# Final.net
KiCad netlist of a schematic drawn in Altium Designer
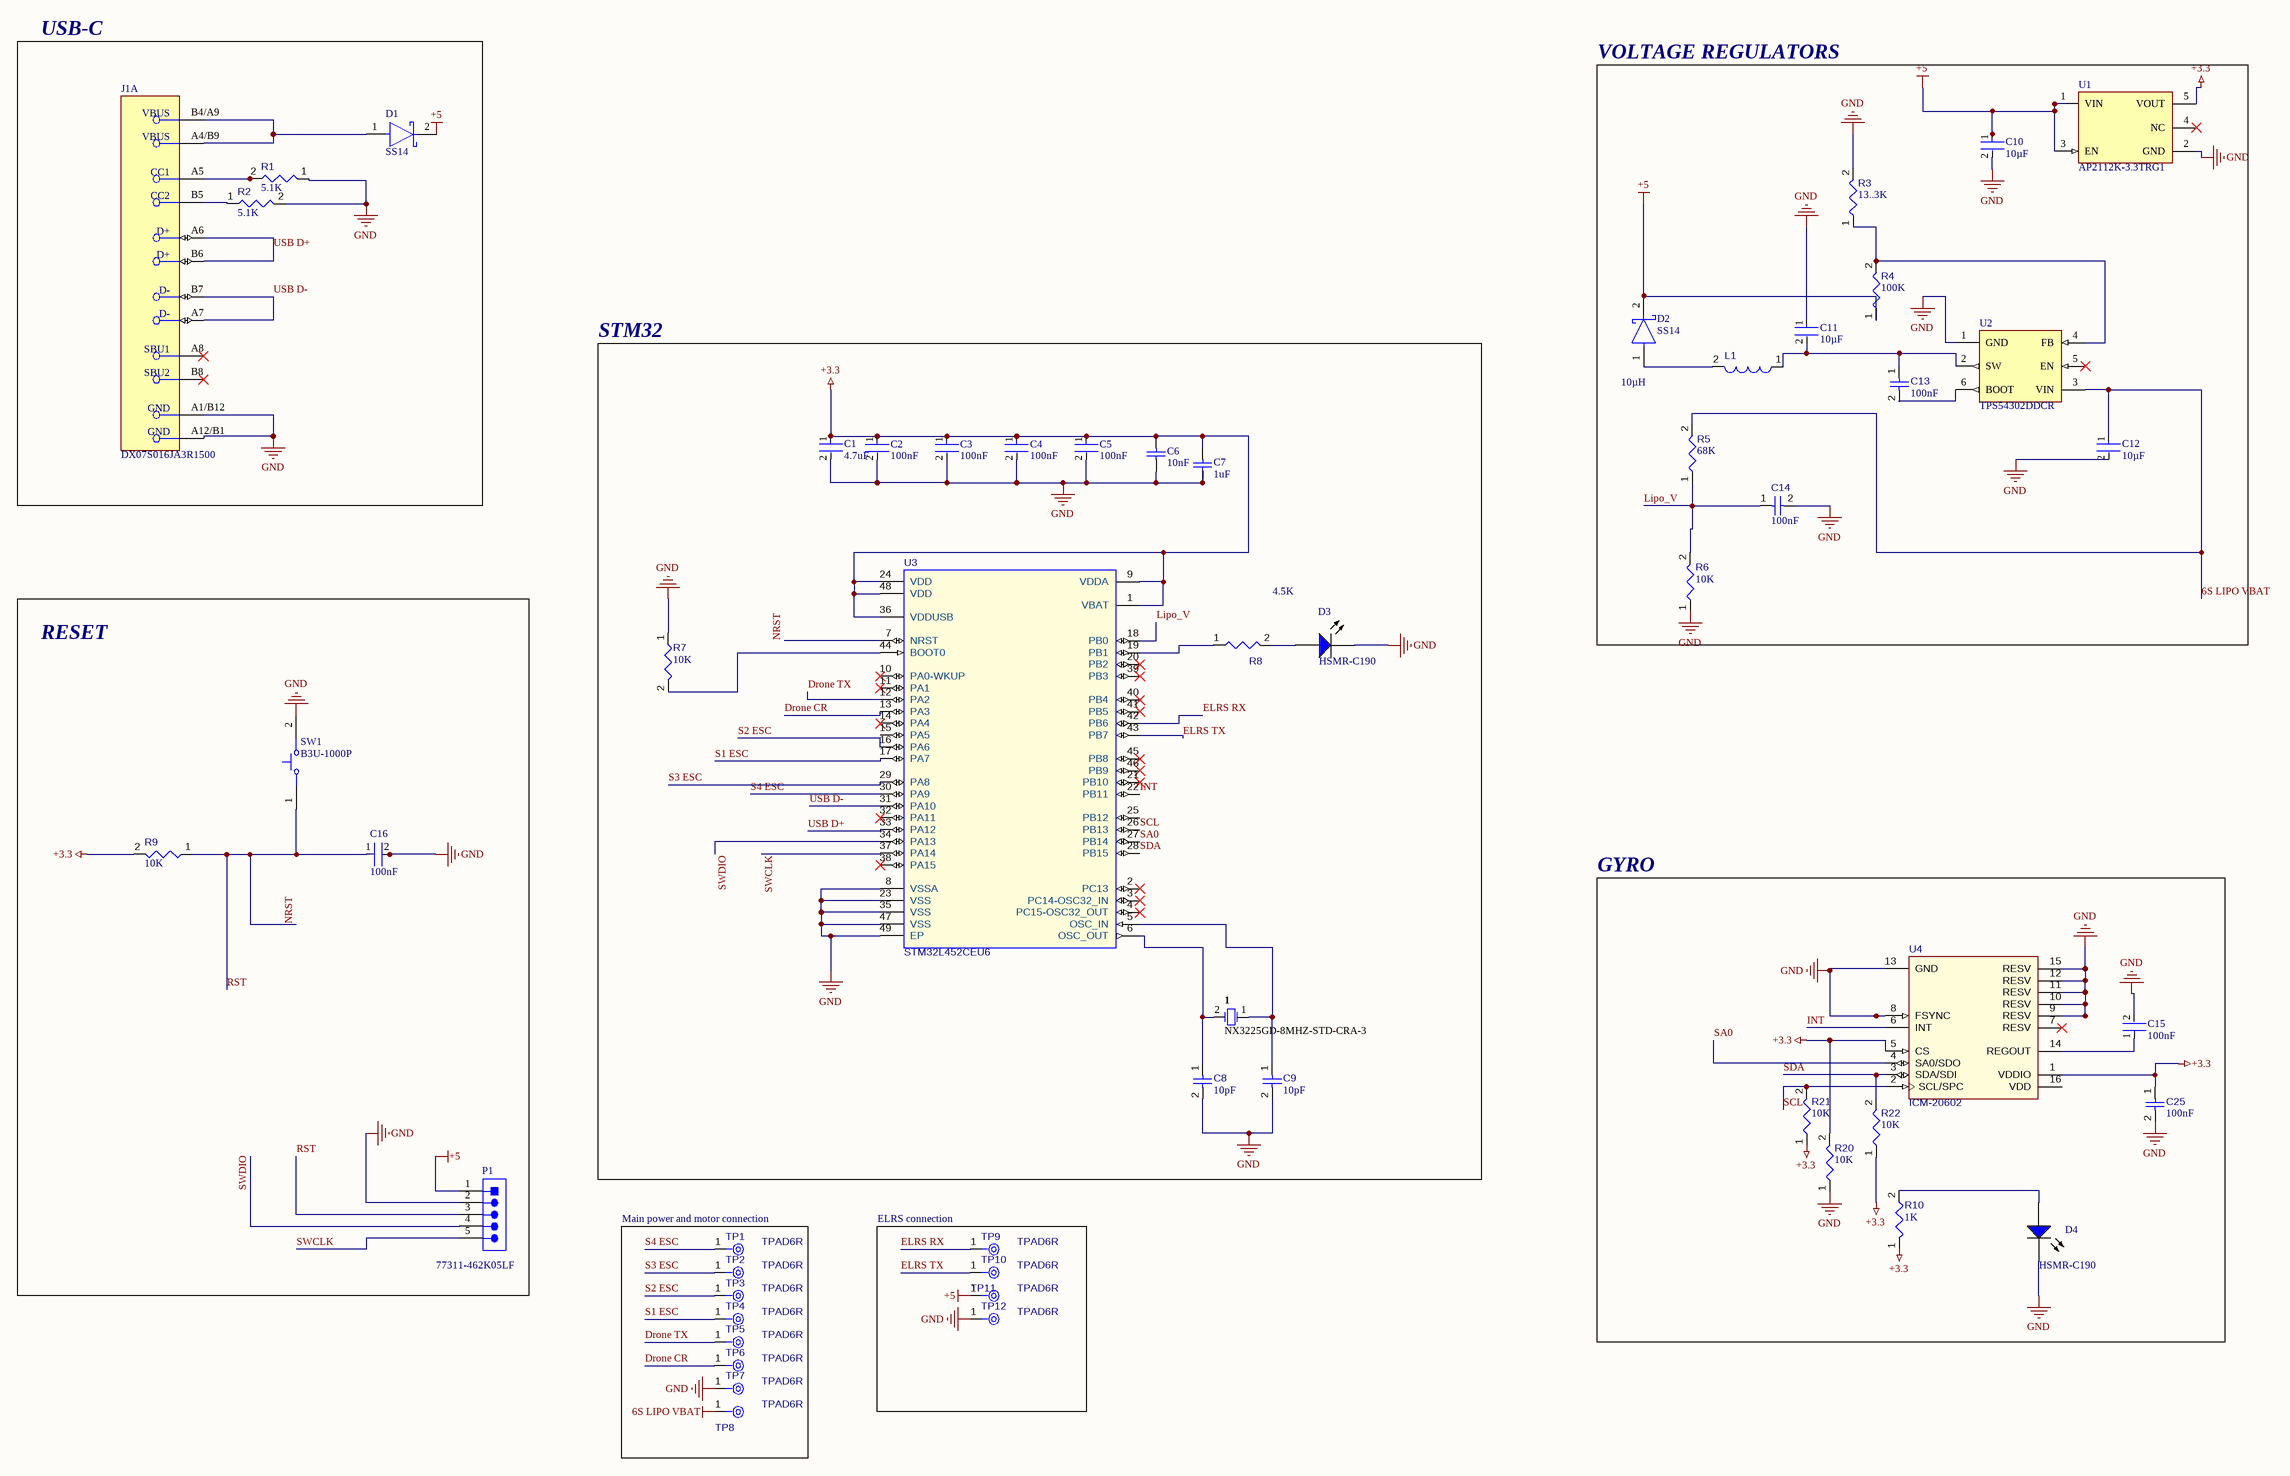
[diagram p0: Final.SchDoc]

(export (version "E")
  (design (tool "Eeschema 10.0.6"))
  (components
    (comp (ref "1")
      (value "NX3225GD-8MHZ-STD-CRA-3")
      (footprint "NDK-NX3225GD-8MHZ-STD-CRA-3_V")
      (description "Crystal Unit, 8 MHz, 8 pF, -40 to 150 degC, 2-Pin SMD, RoHS, Tape and Reel")
      (fields (field (name "MANUFACTURER") "NDK"))
      (libsource (lib "Altium Content Vault") (part "XTAL-1-2-2"))
    )
    (comp (ref "C1")
      (value "4.7uF")
      (footprint "FP-GRM188-0_15-MFG")
      (description "CAP CER 4.7UF 16V X5R 0603")
      (fields (field (name "TOLERANCE") "10%"))
      (libsource (lib "Altium Content Vault") (part "02cd4be3c70576c341d710602a673aa"))
    )
    (comp (ref "C2")
      (value "100nF")
      (footprint "FP-0402YC104KAT2A-MFG")
      (fields (field (name "TOLERANCE") "10%") (field (name "VOLTAGE") "16V"))
      (libsource (lib "Altium Content Vault") (part "02cd4be3c70576c341d710602a673aa"))
    )
    (comp (ref "C3")
      (value "100nF")
      (footprint "FP-0402YC104KAT2A-MFG")
      (fields (field (name "TOLERANCE") "10%") (field (name "VOLTAGE") "16V"))
      (libsource (lib "Altium Content Vault") (part "02cd4be3c70576c341d710602a673aa"))
    )
    (comp (ref "C4")
      (value "100nF")
      (footprint "FP-0402YC104KAT2A-MFG")
      (fields (field (name "TOLERANCE") "10%") (field (name "VOLTAGE") "16V"))
      (libsource (lib "Altium Content Vault") (part "02cd4be3c70576c341d710602a673aa"))
    )
    (comp (ref "C5")
      (value "100nF")
      (footprint "FP-0402YC104KAT2A-MFG")
      (fields (field (name "TOLERANCE") "10%") (field (name "VOLTAGE") "16V"))
      (libsource (lib "Altium Content Vault") (part "02cd4be3c70576c341d710602a673aa"))
    )
    (comp (ref "C6")
      (value "10nF")
      (footprint "CAPC1005X55X25LL05T10")
      (description "Chip Capacitor, 10 nF, 16 V, 10%, -55 to 125 degC, 0402 (1005 Metric), RoHS, Tape and Reel")
      (fields (field (name "MANUFACTURER") "Murata"))
      (libsource (lib "Altium Content Vault") (part "CAP-NP-2"))
    )
    (comp (ref "C7")
      (value "1uF")
      (footprint "CAPC1608X90X35NL10T15")
      (fields (field (name "MANUFACTURER") "Murata") (field (name "PART NUMBER") "GRM188R61C105KA12D"))
      (libsource (lib "Altium Content Vault") (part "CAP"))
    )
    (comp (ref "C8")
      (value "10pF")
      (footprint "CAPC1005X55X25ML05T05")
      (description "Chip Capacitor, 10 pF, +/- 5%, 50 V, 0402 (1005 Metric)")
      (fields (field (name "TOLERANCE") "5%") (field (name "Comment") "Capacitor 10 pF +/- 5% 50 V 0402"))
      (libsource (lib "Johnbright Onyeise") (part "CAP-NP-2"))
    )
    (comp (ref "C9")
      (value "10pF")
      (footprint "CAPC1005X55X25ML05T05")
      (description "Chip Capacitor, 10 pF, +/- 5%, 50 V, 0402 (1005 Metric)")
      (fields (field (name "TOLERANCE") "5%") (field (name "Comment") "Capacitor 10 pF +/- 5% 50 V 0402"))
      (libsource (lib "Johnbright Onyeise") (part "CAP-NP-2"))
    )
    (comp (ref "C10")
      (value "10µF")
      (footprint "FP-0805-L_2_0_0_15-W_1_25-MFG")
      (description "Multilayer Ceramic Capacitor 10 uF 16V X5R 10% SMD 0805 T/R")
      (fields (field (name "TOLERANCE") "10%"))
      (libsource (lib "Altium Content Vault") (part "02cd4be3c70576c341d710602a673aa"))
    )
    (comp (ref "C11")
      (value "10µF")
      (footprint "FP-0805-L_2_0_0_15-W_1_25-MFG")
      (description "Multilayer Ceramic Capacitor 10 uF 16V X5R 10% SMD 0805 T/R")
      (fields (field (name "TOLERANCE") "10%"))
      (libsource (lib "Altium Content Vault") (part "02cd4be3c70576c341d710602a673aa"))
    )
    (comp (ref "C12")
      (value "10µF")
      (footprint "FP-0805-L_2_0_0_15-W_1_25-MFG")
      (description "Multilayer Ceramic Capacitor 10 uF 16V X5R 10% SMD 0805 T/R")
      (fields (field (name "TOLERANCE") "10%"))
      (libsource (lib "Altium Content Vault") (part "02cd4be3c70576c341d710602a673aa"))
    )
    (comp (ref "C13")
      (value "100nF")
      (footprint "CAPC0402(1005)60_L")
      (description "Chip Capacitor, 100nF +/-20%, 50V, 0402, Thickness 0.6 mm")
      (fields (field (name "TOLERANCE") "10%") (field (name "Comment") "Capacitor 100nF +/-20% 50V 0402"))
      (libsource (lib "Johnbright Onyeise") (part "CAP-NP-2"))
    )
    (comp (ref "C14")
      (value "100nF")
      (footprint "CAPC0402(1005)60_L")
      (description "Chip Capacitor, 100nF +/-20%, 50V, 0402, Thickness 0.6 mm")
      (fields (field (name "TOLERANCE") "10%") (field (name "Comment") "Capacitor 100nF +/-20% 50V 0402"))
      (libsource (lib "Johnbright Onyeise") (part "CAP-NP-2"))
    )
    (comp (ref "C15")
      (value "100nF")
      (footprint "FP-0402YC104KAT2A-MFG")
      (fields (field (name "TOLERANCE") "10%") (field (name "VOLTAGE") "16V"))
      (libsource (lib "Altium Content Vault") (part "02cd4be3c70576c341d710602a673aa"))
    )
    (comp (ref "C16")
      (value "100nF")
      (footprint "FP-0402YC104KAT2A-MFG")
      (fields (field (name "TOLERANCE") "10%") (field (name "VOLTAGE") "16V"))
      (libsource (lib "Altium Content Vault") (part "02cd4be3c70576c341d710602a673aa"))
    )
    (comp (ref "C25")
      (value "100nF")
      (footprint "CAPC1005X56X25LL10T15")
      (description "Chip Capacitor, 0.1 uF, +/- 5%, 16 V, 0402 (1005 Metric)")
      (fields (field (name "TOLERANCE") "5%") (field (name "Comment") "Capacitor 0.1 uF +/- 5% 16 V 0402"))
      (libsource (lib "Johnbright Onyeise") (part "CAP-NP-2"))
    )
    (comp (ref "D1")
      (value "SS14")
      (footprint "FP-403AE-MFG")
      (description "DIODE SCHOTTKY 40V 1A SMA")
      (fields
        (field (name "MANUFACTURER") "ON Semiconductor")
        (field (name "OCTOPART") "https://octopart.com/ss14-on+semiconductor-29205033")
      )
      (libsource (lib "Altium Content Vault") (part "360ad2f4ac25a952324d13796385471"))
    )
    (comp (ref "D2")
      (value "SS14")
      (footprint "FP-403AE-MFG")
      (description "DIODE SCHOTTKY 40V 1A SMA")
      (fields
        (field (name "MANUFACTURER") "ON Semiconductor")
        (field (name "OCTOPART") "https://octopart.com/ss14-on+semiconductor-29205033")
      )
      (libsource (lib "Altium Content Vault") (part "360ad2f4ac25a952324d13796385471"))
    )
    (comp (ref "D3")
      (value "HSMR-C190")
      (footprint "AVAG-HSMX-C190_V")
      (description "LED Uni-Color Blue, 78 mW, 20 mA, -40 to 85 degC, 2-Pin SMD, RoHS, Tape and Reel")
      (fields (field (name "POWER") "78mW") (field (name "MANUFACTURER") "Avago"))
      (libsource (lib "Johnbright Onyeise") (part "LED-BLUE-AK-2"))
    )
    (comp (ref "D4")
      (value "HSMR-C190")
      (footprint "AVAG-HSMX-C190_V")
      (description "LED Uni-Color Blue, 78 mW, 20 mA, -40 to 85 degC, 2-Pin SMD, RoHS, Tape and Reel")
      (fields (field (name "POWER") "78mW") (field (name "MANUFACTURER") "Avago"))
      (libsource (lib "Johnbright Onyeise") (part "LED-BLUE-AK-2"))
    )
    (comp (ref "J1")
      (value "DX07S016JA3R1500")
      (footprint "FP-DX07S016JA3R1500-MFG")
      (description "CONN RCP USB2.0 TYP C 24P SMD RA")
      (libsource (lib "Altium Content Vault") (part "86c7019cab7ffbad937e454fd6d8a8a"))
    )
    (comp (ref "L1")
      (value "10µH")
      (footprint "INDC2520X100X60NL20T20")
      (description "Chip Inductor, 2.2 uH, +/- 20%, -55 to 125 degC, 1008 (2520 Metric), RoHS, Tape and Reel")
      (fields (field (name "TOLERANCE") "20%") (field (name "MANUFACTURER") "Murata"))
      (libsource (lib "Johnbright Onyeise") (part "IND-2"))
    )
    (comp (ref "P1")
      (value "77311-462K05LF")
      (footprint "FCI-77311-5_V")
      (fields (field (name "MANUFACTURER") "FCI Electronics"))
      (libsource (lib "Johnbright Onyeise") (part "CN-1P-M-R5"))
    )
    (comp (ref "R1")
      (value "5.1K")
      (footprint "RESC0402(1005)_L")
      (description "Chip Resistor, 2,37 kOhms, +/-1 %, 63 mW, -55 to 155 degC, 0402")
      (fields (field (name "POWER") "63mW") (field (name "TOLERANCE") "1%"))
      (libsource (lib "Johnbright Onyeise") (part "RES-2"))
    )
    (comp (ref "R2")
      (value "5.1K")
      (footprint "RESC0402(1005)_L")
      (description "Chip Resistor, 2,37 kOhms, +/-1 %, 63 mW, -55 to 155 degC, 0402")
      (fields (field (name "POWER") "63mW") (field (name "TOLERANCE") "1%"))
      (libsource (lib "") (part "RES-2_1"))
    )
    (comp (ref "R3")
      (value "13..3K")
      (footprint "RESC0402(1005)_L")
      (description "Chip Resistor, 2,37 kOhms, +/-1 %, 63 mW, -55 to 155 degC, 0402")
      (fields (field (name "POWER") "63mW") (field (name "TOLERANCE") "1%"))
      (libsource (lib "") (part "RES-2_1"))
    )
    (comp (ref "R4")
      (value "100K")
      (footprint "RESC0402(1005)_L")
      (description "100K 0.063W 1% 0402 (1005 Metric)  SMD")
      (fields (field (name "POWER") "63mW") (field (name "TOLERANCE") "1%"))
      (libsource (lib "Johnbright Onyeise") (part "100KR2F"))
    )
    (comp (ref "R5")
      (value "68K")
      (footprint "RESC0402(1005)_L")
      (description "Chip Resistor, 2,37 kOhms, +/-1 %, 63 mW, -55 to 155 degC, 0402")
      (fields (field (name "POWER") "63mW") (field (name "TOLERANCE") "1%"))
      (libsource (lib "") (part "RES-2_1"))
    )
    (comp (ref "R6")
      (value "10K")
      (footprint "RESC0402(1005)_L")
      (description "Chip Resistor, 2,37 kOhms, +/-1 %, 63 mW, -55 to 155 degC, 0402")
      (fields (field (name "POWER") "63mW") (field (name "TOLERANCE") "1%"))
      (libsource (lib "") (part "RES-2_1"))
    )
    (comp (ref "R7")
      (value "10K")
      (footprint "RESC0402(1005)_L")
      (description "Chip Resistor, 2,37 kOhms, +/-1 %, 63 mW, -55 to 155 degC, 0402")
      (fields (field (name "POWER") "63mW") (field (name "TOLERANCE") "1%"))
      (libsource (lib "") (part "RES-2_1"))
    )
    (comp (ref "R8")
      (value "4.5K")
      (footprint "RESC0402(1005)_L")
      (description "Chip Resistor, 2,37 kOhms, +/-1 %, 63 mW, -55 to 155 degC, 0402")
      (fields (field (name "POWER") "63mW") (field (name "TOLERANCE") "1%"))
      (libsource (lib "") (part "RES-2_1"))
    )
    (comp (ref "R9")
      (value "10K")
      (footprint "RESC0402(1005)_L")
      (description "Chip Resistor, 2,37 kOhms, +/-1 %, 63 mW, -55 to 155 degC, 0402")
      (fields (field (name "POWER") "63mW") (field (name "TOLERANCE") "1%"))
      (libsource (lib "") (part "RES-2_1"))
    )
    (comp (ref "R10")
      (value "1K")
      (footprint "RESC0402(1005)_L")
      (description "Chip Resistor, 2,37 kOhms, +/-1 %, 63 mW, -55 to 155 degC, 0402")
      (fields (field (name "POWER") "63mW") (field (name "TOLERANCE") "1%"))
      (libsource (lib "Johnbright Onyeise") (part "RES-2"))
    )
    (comp (ref "R20")
      (value "10K")
      (footprint "RESC0402(1005)_L")
      (description "Chip Resistor, 2,37 kOhms, +/-1 %, 63 mW, -55 to 155 degC, 0402")
      (fields (field (name "POWER") "63mW") (field (name "TOLERANCE") "1%"))
      (libsource (lib "") (part "RES-2_1"))
    )
    (comp (ref "R21")
      (value "10K")
      (footprint "RESC0402(1005)_L")
      (description "Chip Resistor, 2,37 kOhms, +/-1 %, 63 mW, -55 to 155 degC, 0402")
      (fields (field (name "POWER") "63mW") (field (name "TOLERANCE") "1%"))
      (libsource (lib "") (part "RES-2_1"))
    )
    (comp (ref "R22")
      (value "10K")
      (footprint "RESC0402(1005)_L")
      (description "Chip Resistor, 2,37 kOhms, +/-1 %, 63 mW, -55 to 155 degC, 0402")
      (fields (field (name "POWER") "63mW") (field (name "TOLERANCE") "1%"))
      (libsource (lib "") (part "RES-2_1"))
    )
    (comp (ref "SW1")
      (value "B3U-1000P")
      (footprint "OMRON-B3U-1000_V")
      (description "Tactile Switch, SPST-NO, 0.05 A, 12 V, -25 to 70 degC, 2-Pin SMD, RoHS, Tape and Reel")
      (fields (field (name "MANUFACTURER") "Omron Electronic Components"))
      (libsource (lib "Johnbright Onyeise") (part "SW-SPST-NO-2"))
    )
    (comp (ref "TP1")
      (value "TPAD6R")
      (footprint "TP06R")
      (description "0.6mm round")
      (libsource (lib "Johnbright Onyeise") (part "CMP-001-0001-4"))
    )
    (comp (ref "TP2")
      (value "TPAD6R")
      (footprint "TP06R")
      (description "0.6mm round")
      (libsource (lib "Johnbright Onyeise") (part "CMP-001-0001-4"))
    )
    (comp (ref "TP3")
      (value "TPAD6R")
      (footprint "TP06R")
      (description "0.6mm round")
      (libsource (lib "Johnbright Onyeise") (part "CMP-001-0001-4"))
    )
    (comp (ref "TP4")
      (value "TPAD6R")
      (footprint "TP06R")
      (description "0.6mm round")
      (libsource (lib "Johnbright Onyeise") (part "CMP-001-0001-4"))
    )
    (comp (ref "TP5")
      (value "TPAD6R")
      (footprint "TP06R")
      (description "0.6mm round")
      (libsource (lib "Johnbright Onyeise") (part "CMP-001-0001-4"))
    )
    (comp (ref "TP6")
      (value "TPAD6R")
      (footprint "TP06R")
      (description "0.6mm round")
      (libsource (lib "Johnbright Onyeise") (part "CMP-001-0001-4"))
    )
    (comp (ref "TP7")
      (value "TPAD6R")
      (footprint "TP06R")
      (description "0.6mm round")
      (libsource (lib "Johnbright Onyeise") (part "CMP-001-0001-4"))
    )
    (comp (ref "TP8")
      (value "TPAD6R")
      (footprint "TP06R")
      (description "0.6mm round")
      (libsource (lib "Johnbright Onyeise") (part "CMP-001-0001-4"))
    )
    (comp (ref "TP9")
      (value "TPAD6R")
      (footprint "TP06R")
      (description "0.6mm round")
      (libsource (lib "Johnbright Onyeise") (part "CMP-001-0001-4"))
    )
    (comp (ref "TP10")
      (value "TPAD6R")
      (footprint "TP06R")
      (description "0.6mm round")
      (libsource (lib "Johnbright Onyeise") (part "CMP-001-0001-4"))
    )
    (comp (ref "TP11")
      (value "TPAD6R")
      (footprint "TP06R")
      (description "0.6mm round")
      (libsource (lib "Johnbright Onyeise") (part "CMP-001-0001-4"))
    )
    (comp (ref "TP12")
      (value "TPAD6R")
      (footprint "TP06R")
      (description "0.6mm round")
      (libsource (lib "Johnbright Onyeise") (part "CMP-001-0001-4"))
    )
    (comp (ref "U1")
      (value "AP2112K-3.3TRG1")
      (footprint "FP-SOT25-IPC_A")
      (description "IC REG LINEAR 3.3V 600MA SOT25")
      (libsource (lib "Altium Content Vault") (part "c8ab751aee5229183125ab046a11caa"))
    )
    (comp (ref "U2")
      (value "TPS54302DDCR")
      (footprint "FP-DDC0006A-MFG")
      (description "IC REG BUCK ADJ 3A TSOT23-6")
      (fields
        (field (name "MANUFACTURER") "Texas Instruments")
        (field (name "OCTOPART") "https://octopart.com/tps54302ddcr-texas+instruments-74209025")
      )
      (libsource (lib "Altium Content Vault") (part "e6e62595b56d4ede9a2c24ebe42f01f"))
    )
    (comp (ref "U3")
      (value "STM32L452CEU6")
      (footprint "STM-UFQFPN48_N")
      (description "ARM® Cortex®-M4 STM32L4 Microcontroller IC 32-Bit 80MHz 512KB (512K x 8) FLASH 48-UFQFPN (7x7)")
      (libsource (lib "Johnbright Onyeise") (part "CMP-00133-5"))
    )
    (comp (ref "U4")
      (value "ICM-20602")
      (footprint "INSE-I62-16")
      (libsource (lib "Johnbright Onyeise") (part "CMP-00120-6"))
    )
  )
  (nets
    (net (code "1") (name "+3.3") (class "Default")
      (node (ref "C1") (pin "1") (pinfunction "1_1") (pintype "passive"))
      (node (ref "C2") (pin "1") (pinfunction "1_1") (pintype "passive"))
      (node (ref "C25") (pin "1") (pinfunction "1_1") (pintype "passive"))
      (node (ref "C3") (pin "1") (pinfunction "1_1") (pintype "passive"))
      (node (ref "C4") (pin "1") (pinfunction "1_1") (pintype "passive"))
      (node (ref "C5") (pin "1") (pinfunction "1_1") (pintype "passive"))
      (node (ref "C6") (pin "1") (pinfunction "1_1") (pintype "passive"))
      (node (ref "C7") (pin "2") (pinfunction "2_2") (pintype "passive"))
      (node (ref "R10") (pin "1") (pinfunction "1_1") (pintype "passive"))
      (node (ref "R20") (pin "2") (pinfunction "2_2") (pintype "passive"))
      (node (ref "R21") (pin "1") (pinfunction "1_1") (pintype "passive"))
      (node (ref "R22") (pin "1") (pinfunction "1_1") (pintype "passive"))
      (node (ref "R9") (pin "2") (pinfunction "2_2") (pintype "passive"))
      (node (ref "U1") (pin "5") (pinfunction "VOUT_5") (pintype "power_in"))
      (node (ref "U3") (pin "1") (pinfunction "VBAT_1") (pintype "power_in"))
      (node (ref "U3") (pin "24") (pinfunction "VDD_24") (pintype "power_in"))
      (node (ref "U3") (pin "36") (pinfunction "VDDUSB_36") (pintype "power_in"))
      (node (ref "U3") (pin "48") (pinfunction "VDD_48") (pintype "power_in"))
      (node (ref "U3") (pin "9") (pinfunction "VDDA_9") (pintype "power_in"))
      (node (ref "U4") (pin "1") (pinfunction "VDDIO_1") (pintype "power_in"))
      (node (ref "U4") (pin "5") (pinfunction "CS_5") (pintype "input"))
    )
    (net (code "2") (name "+5") (class "Default")
      (node (ref "C10") (pin "1") (pinfunction "1_1") (pintype "passive"))
      (node (ref "D1") (pin "2") (pinfunction "C_2") (pintype "passive"))
      (node (ref "D2") (pin "2") (pinfunction "C_2") (pintype "passive"))
      (node (ref "P1") (pin "1") (pinfunction "DTR_1") (pintype "passive"))
      (node (ref "R4") (pin "1") (pinfunction "1_1") (pintype "passive"))
      (node (ref "TP11") (pin "1") (pinfunction "TP_1") (pintype "passive"))
      (node (ref "U1") (pin "1") (pinfunction "VIN_1") (pintype "power_in"))
      (node (ref "U1") (pin "3") (pinfunction "EN_3") (pintype "input"))
    )
    (net (code "3") (name "/Drone CR") (class "Default")
      (node (ref "TP6") (pin "1") (pinfunction "TP_1") (pintype "passive"))
      (node (ref "U3") (pin "13") (pinfunction "PA3_13") (pintype "bidirectional"))
    )
    (net (code "4") (name "/Drone TX") (class "Default")
      (node (ref "TP5") (pin "1") (pinfunction "TP_1") (pintype "passive"))
      (node (ref "U3") (pin "12") (pinfunction "PA2_12") (pintype "bidirectional"))
    )
    (net (code "5") (name "/ELRS RX") (class "Default")
      (node (ref "TP9") (pin "1") (pinfunction "TP_1") (pintype "passive"))
      (node (ref "U3") (pin "42") (pinfunction "PB6_42") (pintype "bidirectional"))
    )
    (net (code "6") (name "/ELRS TX") (class "Default")
      (node (ref "TP10") (pin "1") (pinfunction "TP_1") (pintype "passive"))
      (node (ref "U3") (pin "43") (pinfunction "PB7_43") (pintype "bidirectional"))
    )
    (net (code "7") (name "/INT") (class "Default")
      (node (ref "U3") (pin "22") (pinfunction "PB11_22") (pintype "bidirectional"))
      (node (ref "U4") (pin "6") (pinfunction "INT_6") (pintype "open_collector"))
    )
    (net (code "8") (name "/Lipo_V") (class "Default")
      (node (ref "C14") (pin "1") (pinfunction "1_1") (pintype "passive"))
      (node (ref "R5") (pin "1") (pinfunction "1_1") (pintype "passive"))
      (node (ref "R6") (pin "2") (pinfunction "2_2") (pintype "passive"))
      (node (ref "U3") (pin "18") (pinfunction "PB0_18") (pintype "bidirectional"))
    )
    (net (code "9") (name "/NRST") (class "Default")
      (node (ref "C16") (pin "1") (pinfunction "1_1") (pintype "passive"))
      (node (ref "P1") (pin "3") (pinfunction "TXO_3") (pintype "passive"))
      (node (ref "R9") (pin "1") (pinfunction "1_1") (pintype "passive"))
      (node (ref "SW1") (pin "1") (pinfunction "1_1") (pintype "passive"))
      (node (ref "U3") (pin "7") (pinfunction "NRST_7") (pintype "bidirectional"))
    )
    (net (code "10") (name "/S1 ESC") (class "Default")
      (node (ref "TP4") (pin "1") (pinfunction "TP_1") (pintype "passive"))
      (node (ref "U3") (pin "17") (pinfunction "PA7_17") (pintype "bidirectional"))
    )
    (net (code "11") (name "/S2 ESC") (class "Default")
      (node (ref "TP3") (pin "1") (pinfunction "TP_1") (pintype "passive"))
      (node (ref "U3") (pin "16") (pinfunction "PA6_16") (pintype "bidirectional"))
    )
    (net (code "12") (name "/S3 ESC") (class "Default")
      (node (ref "TP2") (pin "1") (pinfunction "TP_1") (pintype "passive"))
      (node (ref "U3") (pin "29") (pinfunction "PA8_29") (pintype "bidirectional"))
    )
    (net (code "13") (name "/S4 ESC") (class "Default")
      (node (ref "TP1") (pin "1") (pinfunction "TP_1") (pintype "passive"))
      (node (ref "U3") (pin "30") (pinfunction "PA9_30") (pintype "bidirectional"))
    )
    (net (code "14") (name "/SA0") (class "Default")
      (node (ref "U3") (pin "27") (pinfunction "PB14_27") (pintype "bidirectional"))
      (node (ref "U4") (pin "4") (pinfunction "SA0/SDO_4") (pintype "bidirectional"))
    )
    (net (code "15") (name "/SCL") (class "Default")
      (node (ref "R21") (pin "2") (pinfunction "2_2") (pintype "passive"))
      (node (ref "U3") (pin "26") (pinfunction "PB13_26") (pintype "bidirectional"))
      (node (ref "U4") (pin "2") (pinfunction "SCL/SPC_2") (pintype "input"))
    )
    (net (code "16") (name "/SDA") (class "Default")
      (node (ref "R22") (pin "2") (pinfunction "2_2") (pintype "passive"))
      (node (ref "U3") (pin "28") (pinfunction "PB15_28") (pintype "bidirectional"))
      (node (ref "U4") (pin "3") (pinfunction "SDA/SDI_3") (pintype "bidirectional"))
    )
    (net (code "17") (name "/SWCLK") (class "Default")
      (node (ref "P1") (pin "5") (pinfunction "CTS_5") (pintype "passive"))
      (node (ref "U3") (pin "37") (pinfunction "PA14_37") (pintype "bidirectional"))
    )
    (net (code "18") (name "/SWDIO") (class "Default")
      (node (ref "P1") (pin "4") (pinfunction "VCC_4") (pintype "passive"))
      (node (ref "U3") (pin "34") (pinfunction "PA13_34") (pintype "bidirectional"))
    )
    (net (code "19") (name "/USB D+") (class "Default")
      (node (ref "J1") (pin "A6") (pinfunction "D+_A6") (pintype "bidirectional"))
      (node (ref "J1") (pin "B6") (pinfunction "D+_B6") (pintype "bidirectional"))
      (node (ref "U3") (pin "33") (pinfunction "PA12_33") (pintype "bidirectional"))
    )
    (net (code "20") (name "/USB D-") (class "Default")
      (node (ref "J1") (pin "A7") (pinfunction "D-_A7") (pintype "bidirectional"))
      (node (ref "J1") (pin "B7") (pinfunction "D-_B7") (pintype "bidirectional"))
      (node (ref "U3") (pin "31") (pinfunction "PA10_31") (pintype "bidirectional"))
    )
    (net (code "21") (name "6S LIPO VBAT") (class "Default")
      (node (ref "C12") (pin "1") (pinfunction "1_1") (pintype "passive"))
      (node (ref "R5") (pin "2") (pinfunction "2_2") (pintype "passive"))
      (node (ref "TP8") (pin "1") (pinfunction "TP_1") (pintype "passive"))
      (node (ref "U2") (pin "3") (pinfunction "VIN_3") (pintype "power_in"))
    )
    (net (code "22") (name "GND") (class "Default")
      (node (ref "C1") (pin "2") (pinfunction "2_2") (pintype "passive"))
      (node (ref "C10") (pin "2") (pinfunction "2_2") (pintype "passive"))
      (node (ref "C11") (pin "1") (pinfunction "1_1") (pintype "passive"))
      (node (ref "C12") (pin "2") (pinfunction "2_2") (pintype "passive"))
      (node (ref "C14") (pin "2") (pinfunction "2_2") (pintype "passive"))
      (node (ref "C15") (pin "2") (pinfunction "2_2") (pintype "passive"))
      (node (ref "C16") (pin "2") (pinfunction "2_2") (pintype "passive"))
      (node (ref "C2") (pin "2") (pinfunction "2_2") (pintype "passive"))
      (node (ref "C25") (pin "2") (pinfunction "2_2") (pintype "passive"))
      (node (ref "C3") (pin "2") (pinfunction "2_2") (pintype "passive"))
      (node (ref "C4") (pin "2") (pinfunction "2_2") (pintype "passive"))
      (node (ref "C5") (pin "2") (pinfunction "2_2") (pintype "passive"))
      (node (ref "C6") (pin "2") (pinfunction "2_2") (pintype "passive"))
      (node (ref "C7") (pin "1") (pinfunction "1_1") (pintype "passive"))
      (node (ref "C8") (pin "2") (pinfunction "2_2") (pintype "passive"))
      (node (ref "C9") (pin "2") (pinfunction "2_2") (pintype "passive"))
      (node (ref "D3") (pin "2") (pinfunction "K_2") (pintype "passive"))
      (node (ref "D4") (pin "2") (pinfunction "K_2") (pintype "passive"))
      (node (ref "J1") (pin "A1/B12") (pinfunction "GND_A1/B12") (pintype "power_in"))
      (node (ref "J1") (pin "A12/B1") (pinfunction "GND_A12/B1") (pintype "power_in"))
      (node (ref "P1") (pin "2") (pinfunction "RXI_2") (pintype "passive"))
      (node (ref "R1") (pin "1") (pinfunction "1_1") (pintype "passive"))
      (node (ref "R2") (pin "2") (pinfunction "2_2") (pintype "passive"))
      (node (ref "R20") (pin "1") (pinfunction "1_1") (pintype "passive"))
      (node (ref "R3") (pin "2") (pinfunction "2_2") (pintype "passive"))
      (node (ref "R6") (pin "1") (pinfunction "1_1") (pintype "passive"))
      (node (ref "R7") (pin "1") (pinfunction "1_1") (pintype "passive"))
      (node (ref "SW1") (pin "2") (pinfunction "2_2") (pintype "passive"))
      (node (ref "TP12") (pin "1") (pinfunction "TP_1") (pintype "passive"))
      (node (ref "TP7") (pin "1") (pinfunction "TP_1") (pintype "passive"))
      (node (ref "U1") (pin "2") (pinfunction "GND_2") (pintype "power_in"))
      (node (ref "U2") (pin "1") (pinfunction "GND_1") (pintype "power_in"))
      (node (ref "U3") (pin "23") (pinfunction "VSS_23") (pintype "power_in"))
      (node (ref "U3") (pin "35") (pinfunction "VSS_35") (pintype "power_in"))
      (node (ref "U3") (pin "47") (pinfunction "VSS_47") (pintype "power_in"))
      (node (ref "U3") (pin "49") (pinfunction "EP_49") (pintype "passive"))
      (node (ref "U3") (pin "8") (pinfunction "VSSA_8") (pintype "power_in"))
      (node (ref "U4") (pin "10") (pinfunction "RESV_10") (pintype "passive"))
      (node (ref "U4") (pin "11") (pinfunction "RESV_11") (pintype "passive"))
      (node (ref "U4") (pin "12") (pinfunction "RESV_12") (pintype "passive"))
      (node (ref "U4") (pin "13") (pinfunction "GND_13") (pintype "power_in"))
      (node (ref "U4") (pin "15") (pinfunction "RESV_15") (pintype "passive"))
      (node (ref "U4") (pin "8") (pinfunction "FSYNC_8") (pintype "input"))
      (node (ref "U4") (pin "9") (pinfunction "RESV_9") (pintype "passive"))
    )
    (net (code "23") (name "Net-(D1-A)") (class "Default")
      (node (ref "D1") (pin "1") (pinfunction "A_1") (pintype "passive"))
      (node (ref "J1") (pin "A4/B9") (pinfunction "VBUS_A4/B9") (pintype "power_in"))
      (node (ref "J1") (pin "B4/A9") (pinfunction "VBUS_B4/A9") (pintype "power_in"))
    )
    (net (code "24") (name "Net-(D2-A)") (class "Default")
      (node (ref "D2") (pin "1") (pinfunction "A_1") (pintype "passive"))
      (node (ref "L1") (pin "2") (pinfunction "2_2") (pintype "passive"))
    )
    (net (code "25") (name "Net-(D3-A)") (class "Default")
      (node (ref "D3") (pin "1") (pinfunction "A_1") (pintype "passive"))
      (node (ref "R8") (pin "2") (pinfunction "2_2") (pintype "passive"))
    )
    (net (code "26") (name "Net-(D4-A)") (class "Default")
      (node (ref "D4") (pin "1") (pinfunction "A_1") (pintype "passive"))
      (node (ref "R10") (pin "2") (pinfunction "2_2") (pintype "passive"))
    )
    (net (code "27") (name "Net-(J1A-CC1)") (class "Default")
      (node (ref "J1") (pin "A5") (pinfunction "CC1_A5") (pintype "passive"))
      (node (ref "R1") (pin "2") (pinfunction "2_2") (pintype "passive"))
    )
    (net (code "28") (name "Net-(J1A-CC2)") (class "Default")
      (node (ref "J1") (pin "B5") (pinfunction "CC2_B5") (pintype "passive"))
      (node (ref "R2") (pin "1") (pinfunction "1_1") (pintype "passive"))
    )
    (net (code "29") (name "Net-(U2-BOOT)") (class "Default")
      (node (ref "C13") (pin "2") (pinfunction "2_2") (pintype "passive"))
      (node (ref "U2") (pin "6") (pinfunction "BOOT_6") (pintype "output"))
    )
    (net (code "30") (name "Net-(U2-FB)") (class "Default")
      (node (ref "R3") (pin "1") (pinfunction "1_1") (pintype "passive"))
      (node (ref "R4") (pin "2") (pinfunction "2_2") (pintype "passive"))
      (node (ref "U2") (pin "4") (pinfunction "FB_4") (pintype "input"))
    )
    (net (code "31") (name "Net-(U2-SW)") (class "Default")
      (node (ref "C11") (pin "2") (pinfunction "2_2") (pintype "passive"))
      (node (ref "C13") (pin "1") (pinfunction "1_1") (pintype "passive"))
      (node (ref "L1") (pin "1") (pinfunction "1_1") (pintype "passive"))
      (node (ref "U2") (pin "2") (pinfunction "SW_2") (pintype "output"))
    )
    (net (code "32") (name "Net-(U3-BOOT0)") (class "Default")
      (node (ref "R7") (pin "2") (pinfunction "2_2") (pintype "passive"))
      (node (ref "U3") (pin "44") (pinfunction "BOOT0_44") (pintype "input"))
    )
    (net (code "33") (name "Net-(U3-OSC_IN)") (class "Default")
      (node (ref "1") (pin "1") (pinfunction "1_1") (pintype "passive"))
      (node (ref "C9") (pin "1") (pinfunction "1_1") (pintype "passive"))
      (node (ref "U3") (pin "5") (pinfunction "OSC_IN_5") (pintype "input"))
    )
    (net (code "34") (name "Net-(U3-OSC_OUT)") (class "Default")
      (node (ref "1") (pin "2") (pinfunction "2_2") (pintype "passive"))
      (node (ref "C8") (pin "1") (pinfunction "1_1") (pintype "passive"))
      (node (ref "U3") (pin "6") (pinfunction "OSC_OUT_6") (pintype "output"))
    )
    (net (code "35") (name "Net-(U3-PB1)") (class "Default")
      (node (ref "R8") (pin "1") (pinfunction "1_1") (pintype "passive"))
      (node (ref "U3") (pin "19") (pinfunction "PB1_19") (pintype "bidirectional"))
    )
    (net (code "36") (name "Net-(U4-REGOUT)") (class "Default")
      (node (ref "C15") (pin "1") (pinfunction "1_1") (pintype "passive"))
      (node (ref "U4") (pin "14") (pinfunction "REGOUT_14") (pintype "passive"))
    )
    (net (code "37") (name "unconnected-(J1A-SBU1-PadA8)") (class "Default")
      (node (ref "J1") (pin "A8") (pinfunction "SBU1_A8") (pintype "passive+no_connect"))
    )
    (net (code "38") (name "unconnected-(J1A-SBU2-PadB8)") (class "Default")
      (node (ref "J1") (pin "B8") (pinfunction "SBU2_B8") (pintype "passive+no_connect"))
    )
    (net (code "39") (name "unconnected-(U1-NC-Pad4)") (class "Default")
      (node (ref "U1") (pin "4") (pinfunction "NC_4") (pintype "passive+no_connect"))
    )
    (net (code "40") (name "unconnected-(U2-EN-Pad5)") (class "Default")
      (node (ref "U2") (pin "5") (pinfunction "EN_5") (pintype "input+no_connect"))
    )
    (net (code "41") (name "unconnected-(U3-PA0-WKUP-Pad10)") (class "Default")
      (node (ref "U3") (pin "10") (pinfunction "PA0-WKUP_10") (pintype "bidirectional+no_connect"))
    )
    (net (code "42") (name "unconnected-(U3-PA1-Pad11)") (class "Default")
      (node (ref "U3") (pin "11") (pinfunction "PA1_11") (pintype "bidirectional+no_connect"))
    )
    (net (code "43") (name "unconnected-(U3-PA4-Pad14)") (class "Default")
      (node (ref "U3") (pin "14") (pinfunction "PA4_14") (pintype "bidirectional+no_connect"))
    )
    (net (code "44") (name "unconnected-(U3-PA5-Pad15)") (class "Default")
      (node (ref "U3") (pin "15") (pinfunction "PA5_15") (pintype "bidirectional"))
    )
    (net (code "45") (name "unconnected-(U3-PA11-Pad32)") (class "Default")
      (node (ref "U3") (pin "32") (pinfunction "PA11_32") (pintype "bidirectional+no_connect"))
    )
    (net (code "46") (name "unconnected-(U3-PA15-Pad38)") (class "Default")
      (node (ref "U3") (pin "38") (pinfunction "PA15_38") (pintype "bidirectional+no_connect"))
    )
    (net (code "47") (name "unconnected-(U3-PB2-Pad20)") (class "Default")
      (node (ref "U3") (pin "20") (pinfunction "PB2_20") (pintype "bidirectional+no_connect"))
    )
    (net (code "48") (name "unconnected-(U3-PB3-Pad39)") (class "Default")
      (node (ref "U3") (pin "39") (pinfunction "PB3_39") (pintype "bidirectional+no_connect"))
    )
    (net (code "49") (name "unconnected-(U3-PB4-Pad40)") (class "Default")
      (node (ref "U3") (pin "40") (pinfunction "PB4_40") (pintype "bidirectional+no_connect"))
    )
    (net (code "50") (name "unconnected-(U3-PB5-Pad41)") (class "Default")
      (node (ref "U3") (pin "41") (pinfunction "PB5_41") (pintype "bidirectional+no_connect"))
    )
    (net (code "51") (name "unconnected-(U3-PB8-Pad45)") (class "Default")
      (node (ref "U3") (pin "45") (pinfunction "PB8_45") (pintype "bidirectional+no_connect"))
    )
    (net (code "52") (name "unconnected-(U3-PB9-Pad46)") (class "Default")
      (node (ref "U3") (pin "46") (pinfunction "PB9_46") (pintype "bidirectional+no_connect"))
    )
    (net (code "53") (name "unconnected-(U3-PB10-Pad21)") (class "Default")
      (node (ref "U3") (pin "21") (pinfunction "PB10_21") (pintype "bidirectional+no_connect"))
    )
    (net (code "54") (name "unconnected-(U3-PB12-Pad25)") (class "Default")
      (node (ref "U3") (pin "25") (pinfunction "PB12_25") (pintype "bidirectional"))
    )
    (net (code "55") (name "unconnected-(U3-PC13-Pad2)") (class "Default")
      (node (ref "U3") (pin "2") (pinfunction "PC13_2") (pintype "bidirectional+no_connect"))
    )
    (net (code "56") (name "unconnected-(U3-PC14-OSC32_IN-Pad3)") (class "Default")
      (node (ref "U3") (pin "3") (pinfunction "PC14-OSC32_IN_3") (pintype "bidirectional+no_connect"))
    )
    (net (code "57") (name "unconnected-(U3-PC15-OSC32_OUT-Pad4)") (class "Default")
      (node (ref "U3") (pin "4") (pinfunction "PC15-OSC32_OUT_4") (pintype "bidirectional+no_connect"))
    )
    (net (code "58") (name "unconnected-(U4-RESV-Pad7)") (class "Default")
      (node (ref "U4") (pin "7") (pinfunction "RESV_7") (pintype "passive+no_connect"))
    )
    (net (code "59") (name "unconnected-(U4-VDD-Pad16)") (class "Default")
      (node (ref "U4") (pin "16") (pinfunction "VDD_16") (pintype "power_in"))
    )
  )
)
